# ETH_IFC.net
KiCad netlist of a schematic drawn in Altium Designer
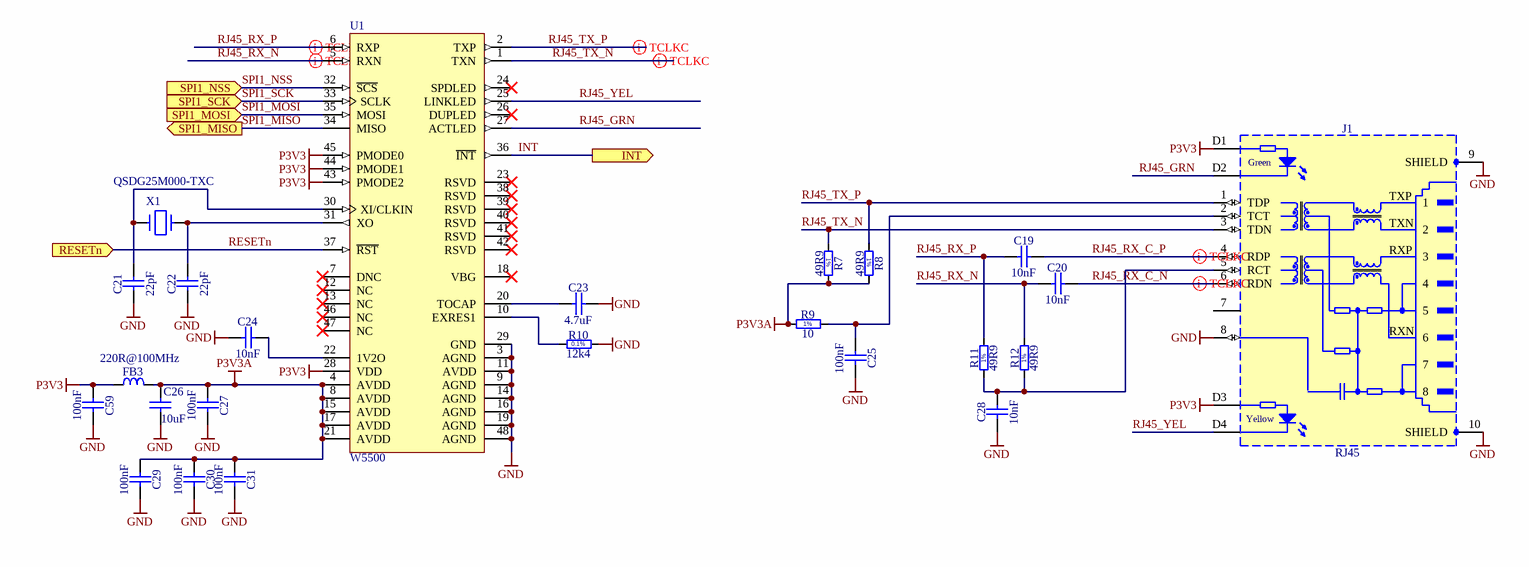
[diagram p0: ETH_IFC.SchDoc]

(export (version "E")
  (design (tool "Eeschema 10.0.6"))
  (components
    (comp (ref "C19")
      (value "10nF")
      (footprint "CAPC1608X87N")
      (description "Non-polarised capacitor")
      (fields
        (field (name "PART NUMBER") "CC0603_10NF_50V_5%_C0G")
        (field (name "VOLTAGE") "50V")
        (field (name "AUTHOR") "CERN DEM JLC")
      )
      (libsource (lib "Capacitors") (part "Capacitor - non polarized"))
    )
    (comp (ref "C20")
      (value "10nF")
      (footprint "CAPC1608X87N")
      (description "Non-polarised capacitor")
      (fields
        (field (name "PART NUMBER") "CC0603_10NF_50V_5%_C0G")
        (field (name "VOLTAGE") "50V")
        (field (name "AUTHOR") "CERN DEM JLC")
      )
      (libsource (lib "Capacitors") (part "Capacitor - non polarized"))
    )
    (comp (ref "C21")
      (value "22pF")
      (footprint "CAPC1005X55N")
      (description "Non-polarised capacitor")
      (fields
        (field (name "PART NUMBER") "CC0402_22PF_50V_5%_NP0")
        (field (name "VOLTAGE") "50V")
        (field (name "AUTHOR") "CERN DEM JLC")
      )
      (libsource (lib "Capacitors") (part "Capacitor - non polarized"))
    )
    (comp (ref "C22")
      (value "22pF")
      (footprint "CAPC1005X55N")
      (description "Non-polarised capacitor")
      (fields
        (field (name "PART NUMBER") "CC0402_22PF_50V_5%_NP0")
        (field (name "VOLTAGE") "50V")
        (field (name "AUTHOR") "CERN DEM JLC")
      )
      (libsource (lib "Capacitors") (part "Capacitor - non polarized"))
    )
    (comp (ref "C23")
      (value "4.7uF")
      (footprint "CAPC1709X95N")
      (description "Non-polarised capacitor")
      (fields
        (field (name "PART NUMBER") "CC0603_4.7UF_16V_10%_X5R")
        (field (name "VOLTAGE") "16V")
        (field (name "AUTHOR") "CERN DEM JLC")
      )
      (libsource (lib "Capacitors") (part "Capacitor - non polarized"))
    )
    (comp (ref "C24")
      (value "10nF")
      (footprint "CAPC1608X87N")
      (description "Non-polarised capacitor")
      (fields
        (field (name "PART NUMBER") "CC0603_10NF_50V_5%_C0G")
        (field (name "VOLTAGE") "50V")
        (field (name "AUTHOR") "CERN DEM JLC")
      )
      (libsource (lib "Capacitors") (part "Capacitor - non polarized"))
    )
    (comp (ref "C25")
      (value "100nF")
      (footprint "CAPC1005X55N")
      (description "Non-polarised capacitor")
      (fields
        (field (name "PART NUMBER") "CC0402_100NF_16V_10%_X7R")
        (field (name "VOLTAGE") "16V")
        (field (name "AUTHOR") "CERN DEM JLC")
      )
      (libsource (lib "Capacitors") (part "Capacitor - non polarized"))
    )
    (comp (ref "C26")
      (value "10uF")
      (footprint "CAPC2012X135N")
      (description "Non-polarised capacitor")
      (fields
        (field (name "PART NUMBER") "CC0805_10UF_10V_10%_X7R")
        (field (name "VOLTAGE") "10V")
        (field (name "AUTHOR") "CERN DEM JLC")
      )
      (libsource (lib "Capacitors") (part "Capacitor - non polarized"))
    )
    (comp (ref "C27")
      (value "100nF")
      (footprint "CAPC1005X55N")
      (description "Non-polarised capacitor")
      (fields
        (field (name "PART NUMBER") "CC0402_100NF_16V_10%_X7R")
        (field (name "VOLTAGE") "16V")
        (field (name "AUTHOR") "CERN DEM JLC")
      )
      (libsource (lib "Capacitors") (part "Capacitor - non polarized"))
    )
    (comp (ref "C28")
      (value "10nF")
      (footprint "CAPC1608X87N")
      (description "Non-polarised capacitor")
      (fields
        (field (name "PART NUMBER") "CC0603_10NF_50V_5%_C0G")
        (field (name "VOLTAGE") "50V")
        (field (name "AUTHOR") "CERN DEM JLC")
      )
      (libsource (lib "Capacitors") (part "Capacitor - non polarized"))
    )
    (comp (ref "C29")
      (value "100nF")
      (footprint "CAPC1005X55N")
      (description "Non-polarised capacitor")
      (fields
        (field (name "PART NUMBER") "CC0402_100NF_16V_10%_X7R")
        (field (name "VOLTAGE") "16V")
        (field (name "AUTHOR") "CERN DEM JLC")
      )
      (libsource (lib "Capacitors") (part "Capacitor - non polarized"))
    )
    (comp (ref "C30")
      (value "100nF")
      (footprint "CAPC1005X55N")
      (description "Non-polarised capacitor")
      (fields
        (field (name "PART NUMBER") "CC0402_100NF_16V_10%_X7R")
        (field (name "VOLTAGE") "16V")
        (field (name "AUTHOR") "CERN DEM JLC")
      )
      (libsource (lib "Capacitors") (part "Capacitor - non polarized"))
    )
    (comp (ref "C31")
      (value "100nF")
      (footprint "CAPC1005X55N")
      (description "Non-polarised capacitor")
      (fields
        (field (name "PART NUMBER") "CC0402_100NF_16V_10%_X7R")
        (field (name "VOLTAGE") "16V")
        (field (name "AUTHOR") "CERN DEM JLC")
      )
      (libsource (lib "Capacitors") (part "Capacitor - non polarized"))
    )
    (comp (ref "C59")
      (value "100nF")
      (footprint "CAPC1005X55N")
      (description "Non-polarised capacitor")
      (fields
        (field (name "PART NUMBER") "CC0402_100NF_16V_10%_X7R")
        (field (name "VOLTAGE") "16V")
        (field (name "AUTHOR") "CERN DEM JLC")
      )
      (libsource (lib "Capacitors") (part "Capacitor - non polarized"))
    )
    (comp (ref "FB3")
      (value "220R@100MHz")
      (footprint "INDC2012X105N")
      (description "Inductor")
      (fields
        (field (name "PART NUMBER") "IND0805_MURATA_BLM21PG221SN1D")
        (field (name "POWER") "2A")
        (field (name "AUTHOR") "CERN DEM JLC")
      )
      (libsource (lib "Inductors & Transformers") (part "Inductor"))
    )
    (comp (ref "J1")
      (value "RJ45")
      (footprint "TYCO_5-6605308-1")
      (fields
        (field (name "PART NUMBER") "TYCO_5-6605308-1")
        (field (name "MANUFACTURER") "TYCO ELECTRONICS")
        (field (name "MANUFACTURER PART NUMBER") "5-6605308-1")
        (field (name "AUTHOR") "CERN DEM JLC")
      )
      (libsource (lib "Connectors") (part "TYCO_5-6605308-1"))
    )
    (comp (ref "R7")
      (value "49R9")
      (footprint "RESC1005X40N")
      (description "Resistor - 1%")
      (fields
        (field (name "PART NUMBER") "R0402_49R9_1%_0.0625W_100PPM")
        (field (name "POWER") "0.0625W")
        (field (name "AUTHOR") "CERN DEM JLC")
      )
      (libsource (lib "Resistors") (part "Resistor - 1%"))
    )
    (comp (ref "R8")
      (value "49R9")
      (footprint "RESC1005X40N")
      (description "Resistor - 1%")
      (fields
        (field (name "PART NUMBER") "R0402_49R9_1%_0.0625W_100PPM")
        (field (name "POWER") "0.0625W")
        (field (name "AUTHOR") "CERN DEM JLC")
      )
      (libsource (lib "Resistors") (part "Resistor - 1%"))
    )
    (comp (ref "R9")
      (value "10")
      (footprint "RESC1005X40N")
      (description "Resistor - 1%")
      (fields
        (field (name "PART NUMBER") "R0402_10R_1%_0.0625W_200PPM")
        (field (name "POWER") "0.0625W")
        (field (name "AUTHOR") "CERN DEM JLC")
      )
      (libsource (lib "Resistors") (part "Resistor - 1%"))
    )
    (comp (ref "R10")
      (value "12k4")
      (footprint "RESC1608X55N")
      (description "Resistor - 0.1%")
      (fields
        (field (name "PART NUMBER") "R0603_12K4_0.1%_0.063W_10PPM")
        (field (name "POWER") "0.063W")
        (field (name "AUTHOR") "CERN DEM JLC")
      )
      (libsource (lib "Resistors") (part "Resistor - 0.1%"))
    )
    (comp (ref "R11")
      (value "49R9")
      (footprint "RESC1005X40N")
      (description "Resistor - 1%")
      (fields
        (field (name "PART NUMBER") "R0402_49R9_1%_0.0625W_100PPM")
        (field (name "POWER") "0.0625W")
        (field (name "AUTHOR") "CERN DEM JLC")
      )
      (libsource (lib "Resistors") (part "Resistor - 1%"))
    )
    (comp (ref "R12")
      (value "49R9")
      (footprint "RESC1005X40N")
      (description "Resistor - 1%")
      (fields
        (field (name "PART NUMBER") "R0402_49R9_1%_0.0625W_100PPM")
        (field (name "POWER") "0.0625W")
        (field (name "AUTHOR") "CERN DEM JLC")
      )
      (libsource (lib "Resistors") (part "Resistor - 1%"))
    )
    (comp (ref "U1")
      (value "W5500")
      (footprint "WIZ-W5500-LQFP-48_M")
      (libsource (lib "Altium Content Vault") (part "WIZ-W5500-LQFP-48"))
    )
    (comp (ref "X1")
      (value "QSDG25M000-TXC")
      (footprint "XTAL_5.0*3.2")
      (description "miniature crystal oscillator (Maritex)")
      (libsource (lib "LIBRARY_SCH") (part "X_CRYSTAL_SMD_5.0*3.2"))
    )
  )
  (nets
    (net (code "1") (name "/INT") (class "Default")
      (node (ref "U1") (pin "36") (pinfunction "~{INT}_36") (pintype "output"))
    )
    (net (code "2") (name "/RESETn") (class "Default")
      (node (ref "U1") (pin "37") (pinfunction "~{RST}_37") (pintype "input"))
    )
    (net (code "3") (name "/RJ45_GRN") (class "Default")
      (node (ref "J1") (pin "D2") (pinfunction "D2_D2") (pintype "passive"))
      (node (ref "U1") (pin "27") (pinfunction "ACTLED_27") (pintype "output"))
    )
    (net (code "4") (name "/RJ45_RX_C_N") (class "Default")
      (node (ref "C20") (pin "2") (pinfunction "2_2") (pintype "passive"))
      (node (ref "J1") (pin "6") (pinfunction "RDN_6") (pintype "bidirectional"))
    )
    (net (code "5") (name "/RJ45_RX_C_P") (class "Default")
      (node (ref "C19") (pin "2") (pinfunction "2_2") (pintype "passive"))
      (node (ref "J1") (pin "4") (pinfunction "RDP_4") (pintype "bidirectional"))
    )
    (net (code "6") (name "/RJ45_RX_N") (class "Default")
      (node (ref "C20") (pin "1") (pinfunction "1_1") (pintype "passive"))
      (node (ref "R12") (pin "2") (pinfunction "2_2") (pintype "passive"))
      (node (ref "U1") (pin "5") (pinfunction "RXN_5") (pintype "input"))
    )
    (net (code "7") (name "/RJ45_RX_P") (class "Default")
      (node (ref "C19") (pin "1") (pinfunction "1_1") (pintype "passive"))
      (node (ref "R11") (pin "2") (pinfunction "2_2") (pintype "passive"))
      (node (ref "U1") (pin "6") (pinfunction "RXP_6") (pintype "input"))
    )
    (net (code "8") (name "/RJ45_TX_N") (class "Default")
      (node (ref "J1") (pin "3") (pinfunction "TDN_3") (pintype "bidirectional"))
      (node (ref "R7") (pin "1") (pinfunction "1_1") (pintype "passive"))
      (node (ref "U1") (pin "1") (pinfunction "TXN_1") (pintype "output"))
    )
    (net (code "9") (name "/RJ45_TX_P") (class "Default")
      (node (ref "J1") (pin "1") (pinfunction "TDP_1") (pintype "bidirectional"))
      (node (ref "R8") (pin "1") (pinfunction "1_1") (pintype "passive"))
      (node (ref "U1") (pin "2") (pinfunction "TXP_2") (pintype "output"))
    )
    (net (code "10") (name "/RJ45_YEL") (class "Default")
      (node (ref "J1") (pin "D4") (pinfunction "D4_D4") (pintype "passive"))
      (node (ref "U1") (pin "25") (pinfunction "LINKLED_25") (pintype "output"))
    )
    (net (code "11") (name "/SPI1_MISO") (class "Default")
      (node (ref "U1") (pin "34") (pinfunction "MISO_34") (pintype "tri_state"))
    )
    (net (code "12") (name "/SPI1_MOSI") (class "Default")
      (node (ref "U1") (pin "35") (pinfunction "MOSI_35") (pintype "input"))
    )
    (net (code "13") (name "/SPI1_NSS") (class "Default")
      (node (ref "U1") (pin "32") (pinfunction "~{SCS}_32") (pintype "input"))
    )
    (net (code "14") (name "/SPI1_SCK") (class "Default")
      (node (ref "U1") (pin "33") (pinfunction "SCLK_33") (pintype "input"))
    )
    (net (code "15") (name "GND") (class "Default")
      (node (ref "C21") (pin "1") (pinfunction "1_1") (pintype "passive"))
      (node (ref "C22") (pin "1") (pinfunction "1_1") (pintype "passive"))
      (node (ref "C23") (pin "2") (pinfunction "2_2") (pintype "passive"))
      (node (ref "C24") (pin "1") (pinfunction "1_1") (pintype "passive"))
      (node (ref "C25") (pin "2") (pinfunction "2_2") (pintype "passive"))
      (node (ref "C26") (pin "2") (pinfunction "2_2") (pintype "passive"))
      (node (ref "C27") (pin "2") (pinfunction "2_2") (pintype "passive"))
      (node (ref "C28") (pin "1") (pinfunction "1_1") (pintype "passive"))
      (node (ref "C29") (pin "2") (pinfunction "2_2") (pintype "passive"))
      (node (ref "C30") (pin "2") (pinfunction "2_2") (pintype "passive"))
      (node (ref "C31") (pin "2") (pinfunction "2_2") (pintype "passive"))
      (node (ref "C59") (pin "2") (pinfunction "2_2") (pintype "passive"))
      (node (ref "J1") (pin "10") (pinfunction "SHIELD_10") (pintype "power_in"))
      (node (ref "J1") (pin "8") (pinfunction "8_8") (pintype "bidirectional"))
      (node (ref "J1") (pin "9") (pinfunction "SHIELD_9") (pintype "power_in"))
      (node (ref "R10") (pin "2") (pinfunction "2_2") (pintype "passive"))
      (node (ref "U1") (pin "11") (pinfunction "AVDD_11") (pintype "power_in"))
      (node (ref "U1") (pin "14") (pinfunction "AGND_14") (pintype "power_in"))
      (node (ref "U1") (pin "16") (pinfunction "AGND_16") (pintype "power_in"))
      (node (ref "U1") (pin "19") (pinfunction "AGND_19") (pintype "power_in"))
      (node (ref "U1") (pin "29") (pinfunction "GND_29") (pintype "power_in"))
      (node (ref "U1") (pin "3") (pinfunction "AGND_3") (pintype "power_in"))
      (node (ref "U1") (pin "48") (pinfunction "AGND_48") (pintype "power_in"))
      (node (ref "U1") (pin "9") (pinfunction "AGND_9") (pintype "power_in"))
    )
    (net (code "16") (name "Net-(J1-RCT)") (class "Default")
      (node (ref "C28") (pin "2") (pinfunction "2_2") (pintype "passive"))
      (node (ref "J1") (pin "5") (pinfunction "RCT_5") (pintype "bidirectional"))
      (node (ref "R11") (pin "1") (pinfunction "1_1") (pintype "passive"))
      (node (ref "R12") (pin "1") (pinfunction "1_1") (pintype "passive"))
    )
    (net (code "17") (name "Net-(J1-TCT)") (class "Default")
      (node (ref "C25") (pin "1") (pinfunction "1_1") (pintype "passive"))
      (node (ref "J1") (pin "2") (pinfunction "TCT_2") (pintype "bidirectional"))
      (node (ref "R9") (pin "2") (pinfunction "2_2") (pintype "passive"))
    )
    (net (code "18") (name "Net-(U1-1V2O)") (class "Default")
      (node (ref "C24") (pin "2") (pinfunction "2_2") (pintype "passive"))
      (node (ref "U1") (pin "22") (pinfunction "1V2O_22") (pintype "power_in"))
    )
    (net (code "19") (name "Net-(U1-EXRES1)") (class "Default")
      (node (ref "R10") (pin "1") (pinfunction "1_1") (pintype "passive"))
      (node (ref "U1") (pin "10") (pinfunction "EXRES1_10") (pintype "passive"))
    )
    (net (code "20") (name "Net-(U1-TOCAP)") (class "Default")
      (node (ref "C23") (pin "1") (pinfunction "1_1") (pintype "passive"))
      (node (ref "U1") (pin "20") (pinfunction "TOCAP_20") (pintype "passive"))
    )
    (net (code "21") (name "Net-(U1-XI{slash}CLKIN)") (class "Default")
      (node (ref "C21") (pin "2") (pinfunction "2_2") (pintype "passive"))
      (node (ref "U1") (pin "30") (pinfunction "XI/CLKIN_30") (pintype "input"))
      (node (ref "X1") (pin "1") (pinfunction "1_1") (pintype "passive"))
    )
    (net (code "22") (name "Net-(U1-XO)") (class "Default")
      (node (ref "C22") (pin "2") (pinfunction "2_2") (pintype "passive"))
      (node (ref "U1") (pin "31") (pinfunction "XO_31") (pintype "output"))
      (node (ref "X1") (pin "2") (pinfunction "2_2") (pintype "passive"))
    )
    (net (code "23") (name "P3V3") (class "Default")
      (node (ref "C59") (pin "1") (pinfunction "1_1") (pintype "passive"))
      (node (ref "FB3") (pin "1") (pinfunction "1_1") (pintype "passive"))
      (node (ref "J1") (pin "D1") (pinfunction "D1_D1") (pintype "passive"))
      (node (ref "J1") (pin "D3") (pinfunction "D3_D3") (pintype "passive"))
      (node (ref "U1") (pin "28") (pinfunction "VDD_28") (pintype "power_in"))
      (node (ref "U1") (pin "43") (pinfunction "PMODE2_43") (pintype "input"))
      (node (ref "U1") (pin "44") (pinfunction "PMODE1_44") (pintype "input"))
      (node (ref "U1") (pin "45") (pinfunction "PMODE0_45") (pintype "input"))
    )
    (net (code "24") (name "P3V3A") (class "Default")
      (node (ref "C26") (pin "1") (pinfunction "1_1") (pintype "passive"))
      (node (ref "C27") (pin "1") (pinfunction "1_1") (pintype "passive"))
      (node (ref "C29") (pin "1") (pinfunction "1_1") (pintype "passive"))
      (node (ref "C30") (pin "1") (pinfunction "1_1") (pintype "passive"))
      (node (ref "C31") (pin "1") (pinfunction "1_1") (pintype "passive"))
      (node (ref "FB3") (pin "2") (pinfunction "2_2") (pintype "passive"))
      (node (ref "R7") (pin "2") (pinfunction "2_2") (pintype "passive"))
      (node (ref "R8") (pin "2") (pinfunction "2_2") (pintype "passive"))
      (node (ref "R9") (pin "1") (pinfunction "1_1") (pintype "passive"))
      (node (ref "U1") (pin "15") (pinfunction "AVDD_15") (pintype "power_in"))
      (node (ref "U1") (pin "17") (pinfunction "AVDD_17") (pintype "power_in"))
      (node (ref "U1") (pin "21") (pinfunction "AVDD_21") (pintype "power_in"))
      (node (ref "U1") (pin "4") (pinfunction "AVDD_4") (pintype "power_in"))
      (node (ref "U1") (pin "8") (pinfunction "AVDD_8") (pintype "power_in"))
    )
    (net (code "25") (name "unconnected-(J1-Pad7)") (class "Default")
      (node (ref "J1") (pin "7") (pinfunction "7_7") (pintype "passive"))
    )
    (net (code "26") (name "unconnected-(U1-DNC-Pad7)") (class "Default")
      (node (ref "U1") (pin "7") (pinfunction "DNC_7") (pintype "passive+no_connect"))
    )
    (net (code "27") (name "unconnected-(U1-DUPLED-Pad26)") (class "Default")
      (node (ref "U1") (pin "26") (pinfunction "DUPLED_26") (pintype "output+no_connect"))
    )
    (net (code "28") (name "unconnected-(U1-NC-Pad12)") (class "Default")
      (node (ref "U1") (pin "12") (pinfunction "NC_12") (pintype "passive+no_connect"))
    )
    (net (code "29") (name "unconnected-(U1-NC-Pad13)") (class "Default")
      (node (ref "U1") (pin "13") (pinfunction "NC_13") (pintype "passive+no_connect"))
    )
    (net (code "30") (name "unconnected-(U1-NC-Pad46)") (class "Default")
      (node (ref "U1") (pin "46") (pinfunction "NC_46") (pintype "passive+no_connect"))
    )
    (net (code "31") (name "unconnected-(U1-NC-Pad47)") (class "Default")
      (node (ref "U1") (pin "47") (pinfunction "NC_47") (pintype "passive+no_connect"))
    )
    (net (code "32") (name "unconnected-(U1-RSVD-Pad23)") (class "Default")
      (node (ref "U1") (pin "23") (pinfunction "RSVD_23") (pintype "passive+no_connect"))
    )
    (net (code "33") (name "unconnected-(U1-RSVD-Pad38)") (class "Default")
      (node (ref "U1") (pin "38") (pinfunction "RSVD_38") (pintype "passive+no_connect"))
    )
    (net (code "34") (name "unconnected-(U1-RSVD-Pad39)") (class "Default")
      (node (ref "U1") (pin "39") (pinfunction "RSVD_39") (pintype "passive+no_connect"))
    )
    (net (code "35") (name "unconnected-(U1-RSVD-Pad40)") (class "Default")
      (node (ref "U1") (pin "40") (pinfunction "RSVD_40") (pintype "passive+no_connect"))
    )
    (net (code "36") (name "unconnected-(U1-RSVD-Pad41)") (class "Default")
      (node (ref "U1") (pin "41") (pinfunction "RSVD_41") (pintype "passive+no_connect"))
    )
    (net (code "37") (name "unconnected-(U1-RSVD-Pad42)") (class "Default")
      (node (ref "U1") (pin "42") (pinfunction "RSVD_42") (pintype "passive+no_connect"))
    )
    (net (code "38") (name "unconnected-(U1-SPDLED-Pad24)") (class "Default")
      (node (ref "U1") (pin "24") (pinfunction "SPDLED_24") (pintype "output+no_connect"))
    )
    (net (code "39") (name "unconnected-(U1-VBG-Pad18)") (class "Default")
      (node (ref "U1") (pin "18") (pinfunction "VBG_18") (pintype "passive+no_connect"))
    )
  )
)
